# IMX291.net
KiCad netlist of a schematic drawn in Altium Designer
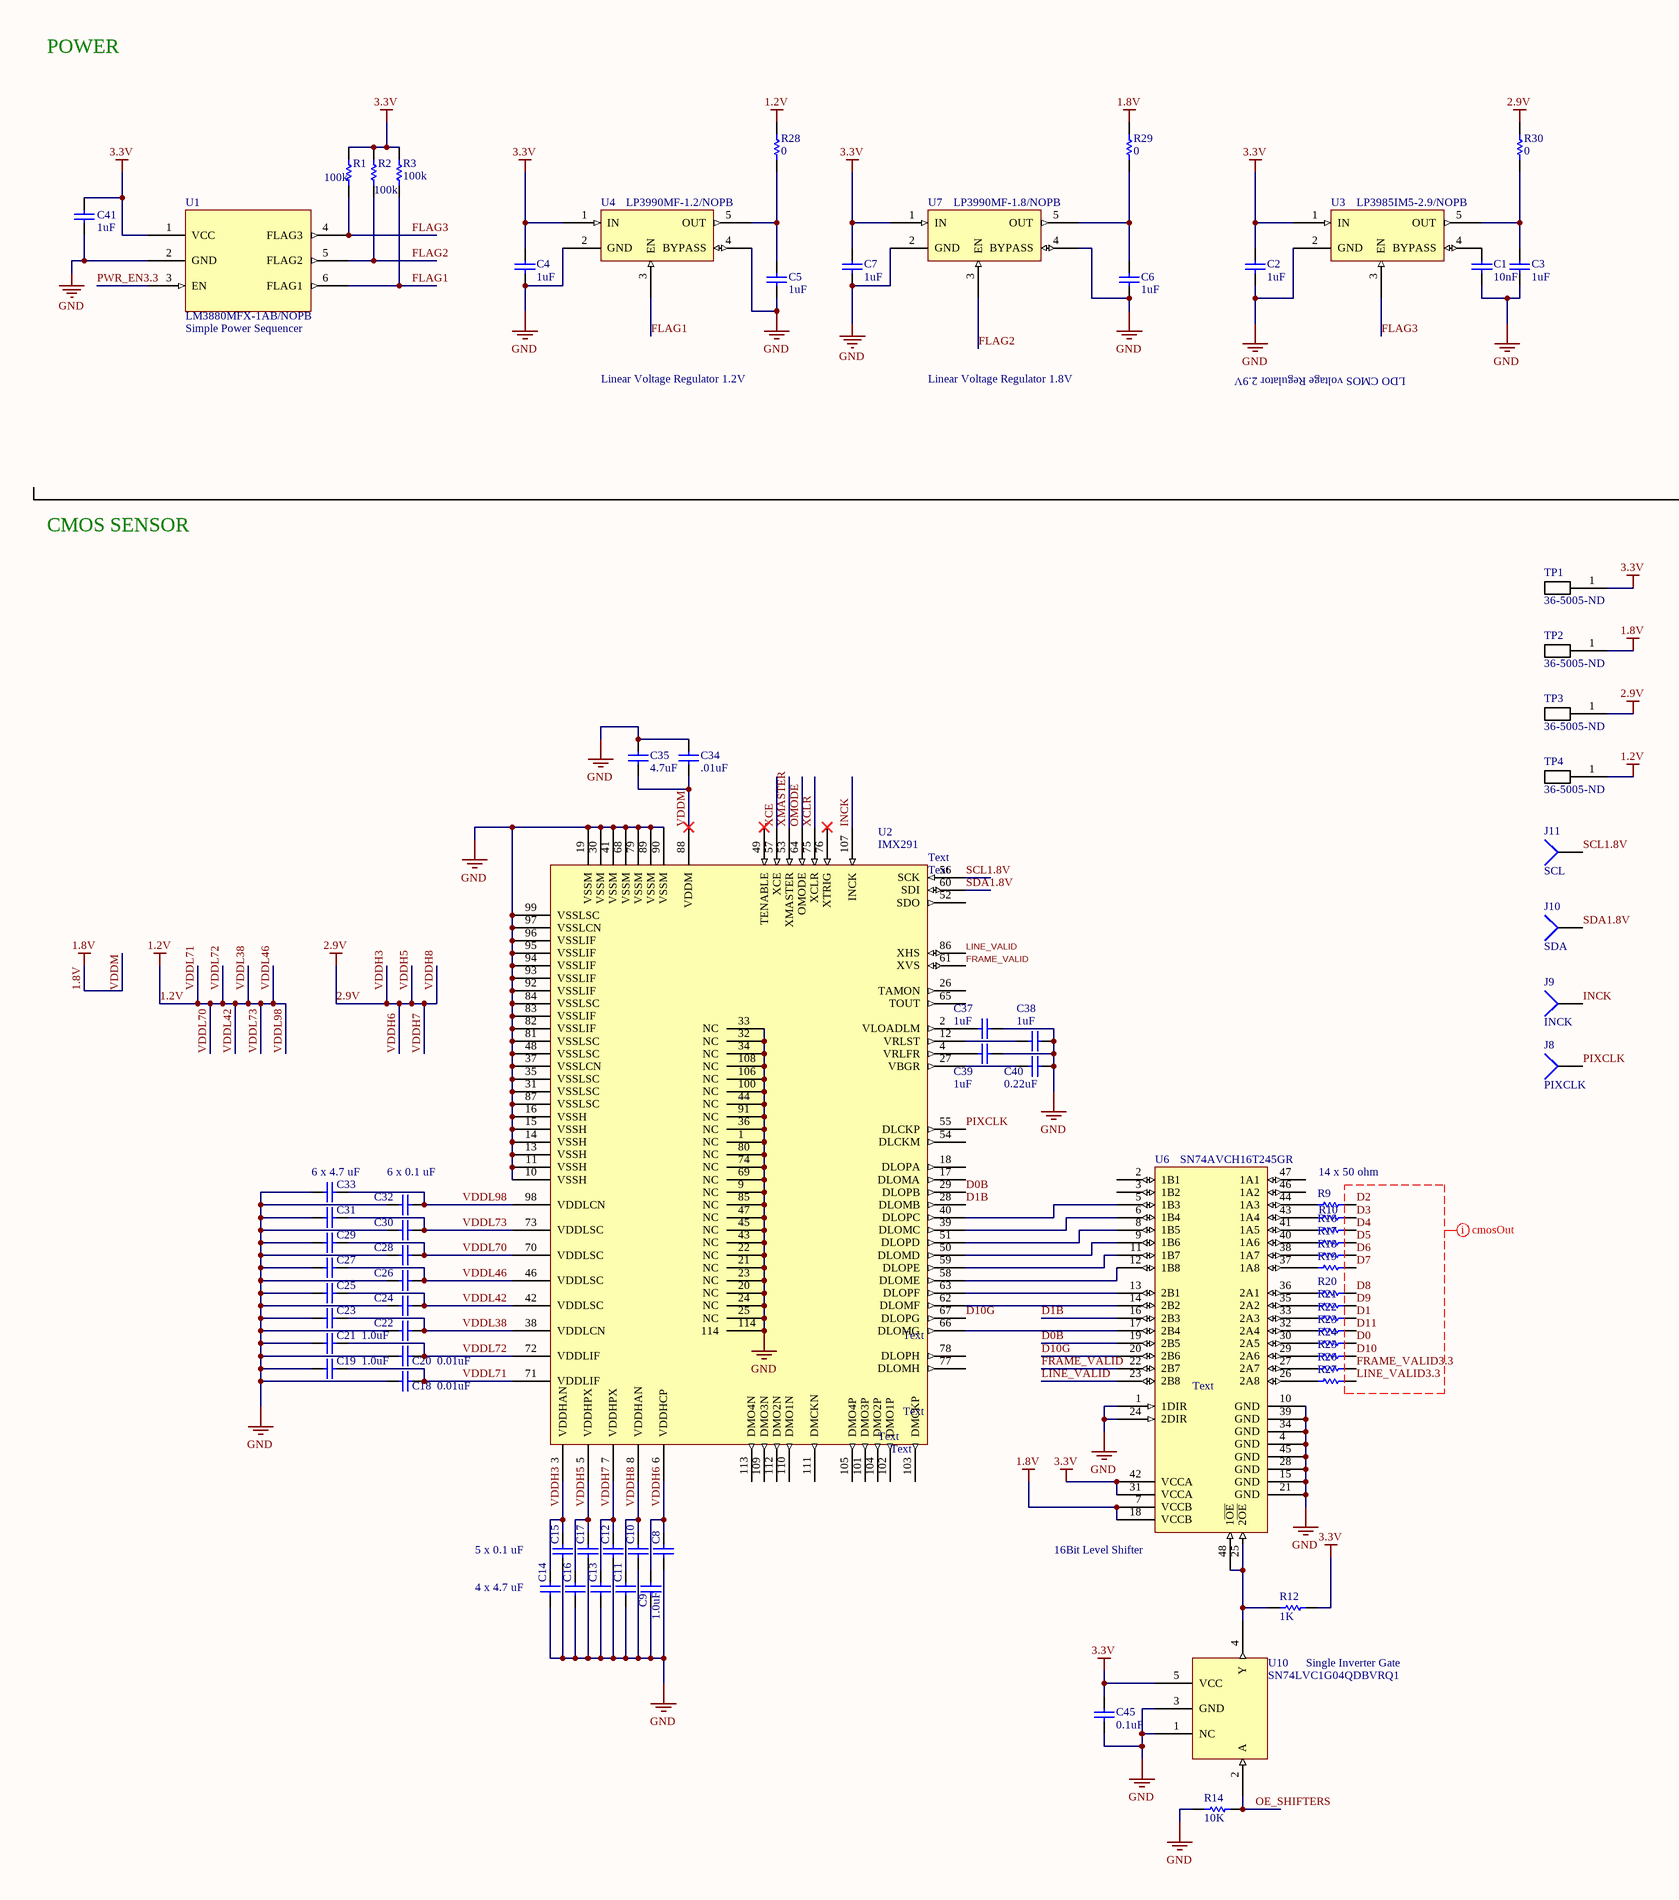
[diagram p0: IMX291.SchDoc, left]
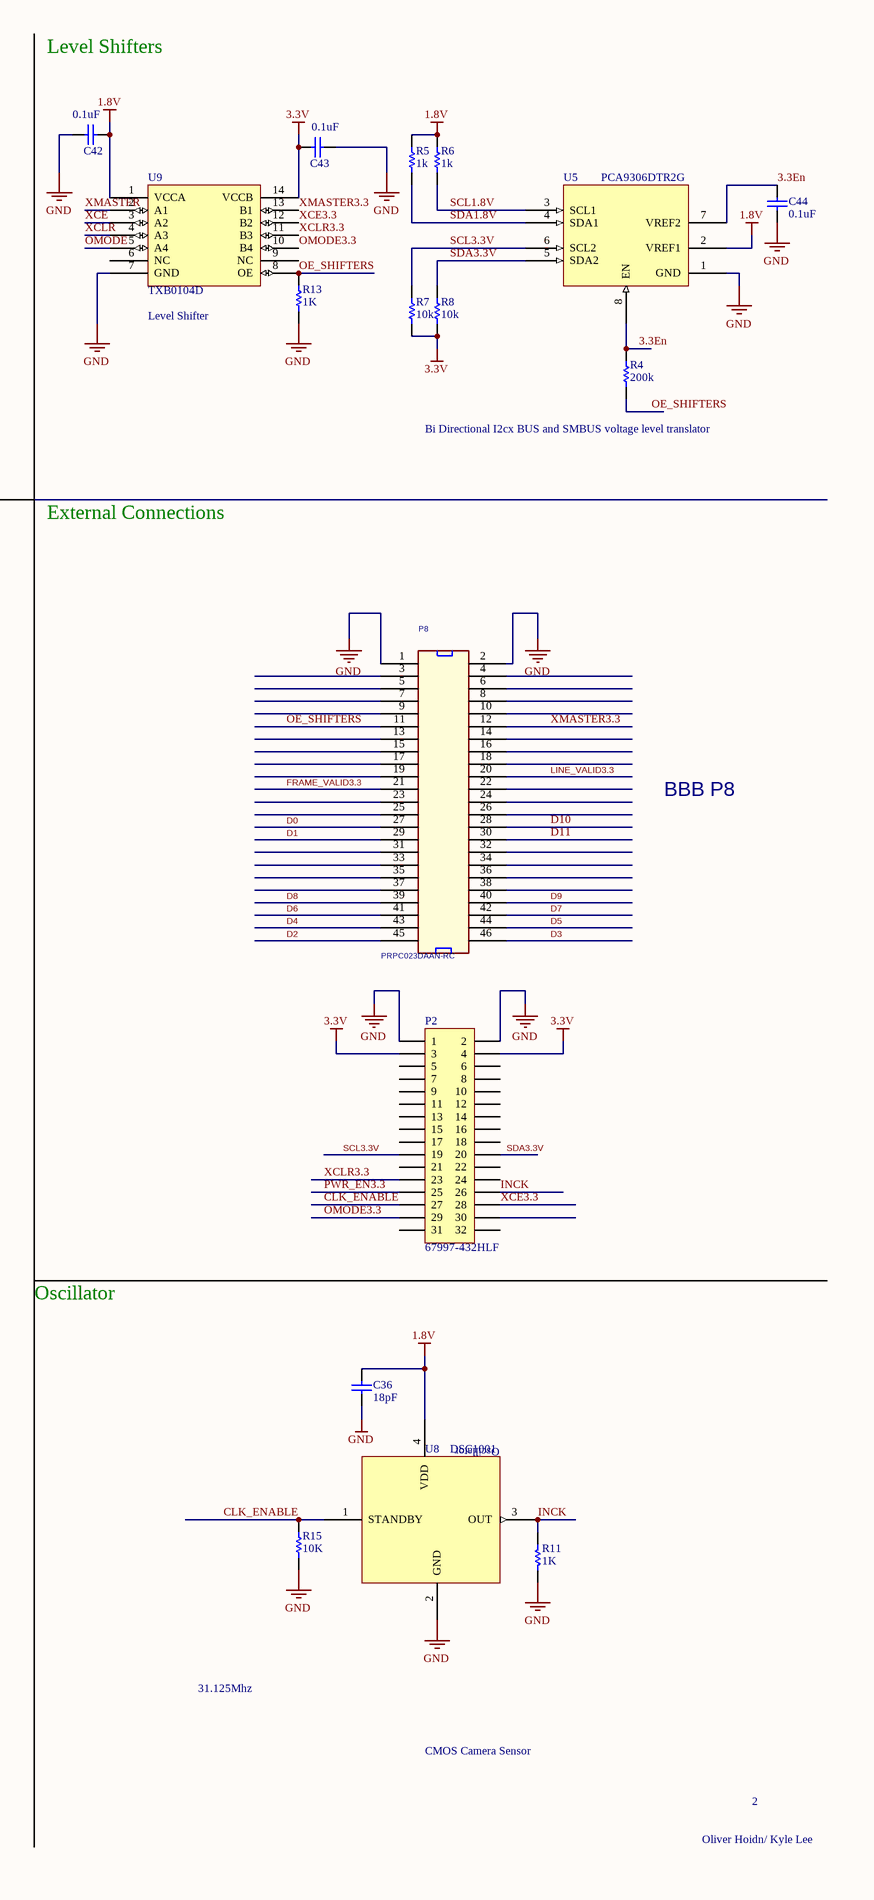
[diagram p1: IMX291.SchDoc, right]

(export (version "E")
  (design (tool "Eeschema 10.0.6"))
  (components
    (comp (ref "C1") (value "10nF") (footprint "0402") (libsource (lib "IMX291") (part "cap")))
    (comp (ref "C2") (value "1uF") (footprint "0402") (libsource (lib "IMX291") (part "cap")))
    (comp (ref "C3") (value "1uF") (footprint "0402") (libsource (lib "IMX291") (part "cap")))
    (comp (ref "C4") (value "1uF") (footprint "0402") (libsource (lib "IMX291") (part "cap")))
    (comp (ref "C5") (value "1uF") (footprint "0402") (libsource (lib "IMX291") (part "cap")))
    (comp (ref "C6") (value "1uF") (footprint "0402") (libsource (lib "IMX291") (part "cap")))
    (comp (ref "C7") (value "1uF") (footprint "0402") (libsource (lib "IMX291") (part "cap")))
    (comp (ref "C8") (value "0.1uF") (footprint "0402") (libsource (lib "IMX291") (part "cap")))
    (comp (ref "C9") (value "1.0uF") (footprint "0402") (libsource (lib "IMX291") (part "cap")))
    (comp (ref "C10") (value "0.1uF") (footprint "0402") (libsource (lib "IMX291") (part "cap")))
    (comp (ref "C11") (value "4.7uF") (footprint "0402") (libsource (lib "IMX291") (part "cap")))
    (comp (ref "C12") (value "0.1uF") (footprint "0402") (libsource (lib "IMX291") (part "cap")))
    (comp (ref "C13") (value "4.7uF") (footprint "0402") (libsource (lib "IMX291") (part "cap")))
    (comp (ref "C14") (value "4.7uF") (footprint "0402") (libsource (lib "IMX291") (part "cap")))
    (comp (ref "C15") (value "0.1uF") (footprint "0402") (libsource (lib "IMX291") (part "cap")))
    (comp (ref "C16") (value "4.7uF") (footprint "0402") (libsource (lib "IMX291") (part "cap")))
    (comp (ref "C17") (value "0.1uF") (footprint "0402") (libsource (lib "IMX291") (part "cap")))
    (comp (ref "C18") (value "0.01uF") (footprint "0402") (libsource (lib "IMX291") (part "cap")))
    (comp (ref "C19") (value "1.0uF") (footprint "0402") (libsource (lib "IMX291") (part "cap")))
    (comp (ref "C20") (value "0.01uF") (footprint "0402") (libsource (lib "IMX291") (part "cap")))
    (comp (ref "C21") (value "1.0uF") (footprint "0402") (libsource (lib "IMX291") (part "cap")))
    (comp (ref "C22") (value "0.1uF") (footprint "0402") (libsource (lib "IMX291") (part "cap")))
    (comp (ref "C23") (value "4.7uF") (footprint "0402") (libsource (lib "IMX291") (part "cap")))
    (comp (ref "C24") (value "0.1uF") (footprint "0402") (libsource (lib "IMX291") (part "cap")))
    (comp (ref "C25") (value "4.7uF") (footprint "0402") (libsource (lib "IMX291") (part "cap")))
    (comp (ref "C26") (value "0.1uF") (footprint "0402") (libsource (lib "IMX291") (part "cap")))
    (comp (ref "C27") (value "4.7uF") (footprint "0402") (libsource (lib "IMX291") (part "cap")))
    (comp (ref "C28") (value "0.1uF") (footprint "0402") (libsource (lib "IMX291") (part "cap")))
    (comp (ref "C29") (value "4.7uF") (footprint "0402") (libsource (lib "IMX291") (part "cap")))
    (comp (ref "C30") (value "0.1uF") (footprint "0402") (libsource (lib "IMX291") (part "cap")))
    (comp (ref "C31") (value "4.7uF") (footprint "0402") (libsource (lib "IMX291") (part "cap")))
    (comp (ref "C32") (value "0.1uF") (footprint "0402") (libsource (lib "IMX291") (part "cap")))
    (comp (ref "C33") (value "4.7uF") (footprint "0402") (libsource (lib "IMX291") (part "cap")))
    (comp (ref "C34") (value ".01uF") (footprint "0402") (libsource (lib "IMX291") (part "cap")))
    (comp (ref "C35") (value "4.7uF") (footprint "0402") (libsource (lib "IMX291") (part "cap")))
    (comp (ref "C36") (value "18pF") (footprint "0402") (libsource (lib "IMX291") (part "cap")))
    (comp (ref "C37") (value "1uF") (footprint "0402") (libsource (lib "IMX291") (part "cap")))
    (comp (ref "C38") (value "1uF") (footprint "0402") (libsource (lib "IMX291") (part "cap")))
    (comp (ref "C39") (value "1uF") (footprint "0402") (libsource (lib "IMX291") (part "cap")))
    (comp (ref "C40") (value "0.22uF") (footprint "0402") (libsource (lib "IMX291") (part "cap")))
    (comp (ref "C41") (value "1uF") (footprint "0402") (libsource (lib "IMX291") (part "cap")))
    (comp (ref "C42") (value "0.1uF") (footprint "0603") (libsource (lib "IMX291") (part "cap")))
    (comp (ref "C43") (value "0.1uF") (footprint "0603") (libsource (lib "IMX291") (part "cap")))
    (comp (ref "C44") (value "0.1uF") (footprint "0402") (libsource (lib "IMX291") (part "cap")))
    (comp (ref "C45") (value "0.1uF") (footprint "0402") (libsource (lib "IMX291") (part "cap")))
    (comp (ref "J8")
      (value "PIXCLK")
      (footprint "PIN1")
      (description "Socket")
      (fields (field (name "PUBLISHER") "Altium Limited"))
      (libsource (lib "IMX291") (part "Socket"))
    )
    (comp (ref "J9")
      (value "INCK")
      (footprint "PIN1")
      (description "Socket")
      (fields (field (name "PUBLISHER") "Altium Limited"))
      (libsource (lib "IMX291") (part "Socket"))
    )
    (comp (ref "J10")
      (value "SDA")
      (footprint "PIN1")
      (description "Socket")
      (fields (field (name "PUBLISHER") "Altium Limited"))
      (libsource (lib "IMX291") (part "Socket"))
    )
    (comp (ref "J11")
      (value "SCL")
      (footprint "PIN1")
      (description "Socket")
      (fields (field (name "PUBLISHER") "Altium Limited"))
      (libsource (lib "IMX291") (part "Socket"))
    )
    (comp (ref "P2")
      (value "67997-432HLF")
      (footprint "HDR2X16")
      (description "P9")
      (fields (field (name "PUBLISHER") "Altium Limited"))
      (libsource (lib "IMX291") (part "Header 16X2"))
    )
    (comp (ref "P8")
      (value "PRPC023DAAN-RC")
      (description "CONN HEADER FMAL 46PS.1\" DL GOLD")
      (fields
        (field (name "MANUFACTURER") "Sullins Connector Solutions")
        (field (name "MANUFACTURER PART NUMBER") "PPPC232LFBN-RC")
      )
      (libsource (lib "IMX291") (part "HDR_46_F_2_0.1_0.1"))
    )
    (comp (ref "R1")
      (value "100k")
      (footprint "0402")
      (description "resistor")
      (libsource (lib "") (part "res_1"))
    )
    (comp (ref "R2")
      (value "100k")
      (footprint "0402")
      (description "resistor")
      (libsource (lib "") (part "res_1"))
    )
    (comp (ref "R3")
      (value "100k")
      (footprint "0402")
      (description "resistor")
      (libsource (lib "") (part "res_1"))
    )
    (comp (ref "R4")
      (value "200k")
      (footprint "0402")
      (description "resistor")
      (libsource (lib "") (part "res_1"))
    )
    (comp (ref "R5")
      (value "1k")
      (footprint "0402")
      (description "resistor")
      (libsource (lib "") (part "res_1"))
    )
    (comp (ref "R6")
      (value "1k")
      (footprint "0402")
      (description "resistor")
      (libsource (lib "") (part "res_1"))
    )
    (comp (ref "R7")
      (value "10k")
      (footprint "0603")
      (description "resistor")
      (libsource (lib "") (part "res_1"))
    )
    (comp (ref "R8")
      (value "10k")
      (footprint "0603")
      (description "resistor")
      (libsource (lib "") (part "res_1"))
    )
    (comp (ref "R9") (value "50") (footprint "0402") (libsource (lib "IMX291") (part "res")))
    (comp (ref "R10") (value "50") (footprint "0402") (libsource (lib "IMX291") (part "res")))
    (comp (ref "R11") (value "1K") (footprint "0402") (libsource (lib "IMX291") (part "res")))
    (comp (ref "R12") (value "1K") (footprint "0402") (libsource (lib "IMX291") (part "res")))
    (comp (ref "R13") (value "1K") (footprint "0402") (libsource (lib "IMX291") (part "res")))
    (comp (ref "R14") (value "10K") (footprint "0402") (libsource (lib "IMX291") (part "res")))
    (comp (ref "R15") (value "10K") (footprint "0402") (libsource (lib "IMX291") (part "res")))
    (comp (ref "R16") (value "50") (footprint "0402") (libsource (lib "IMX291") (part "res")))
    (comp (ref "R17") (value "50") (footprint "0402") (libsource (lib "IMX291") (part "res")))
    (comp (ref "R18") (value "50") (footprint "0402") (libsource (lib "IMX291") (part "res")))
    (comp (ref "R19") (value "50") (footprint "0402") (libsource (lib "IMX291") (part "res")))
    (comp (ref "R20") (value "50") (footprint "0402") (libsource (lib "IMX291") (part "res")))
    (comp (ref "R21") (value "50") (footprint "0402") (libsource (lib "IMX291") (part "res")))
    (comp (ref "R22") (value "50") (footprint "0402") (libsource (lib "IMX291") (part "res")))
    (comp (ref "R23") (value "50") (footprint "0402") (libsource (lib "IMX291") (part "res")))
    (comp (ref "R24") (value "50") (footprint "0402") (libsource (lib "IMX291") (part "res")))
    (comp (ref "R25") (value "50") (footprint "0402") (libsource (lib "IMX291") (part "res")))
    (comp (ref "R26") (value "50") (footprint "0402") (libsource (lib "IMX291") (part "res")))
    (comp (ref "R27") (value "50") (footprint "0402") (libsource (lib "IMX291") (part "res")))
    (comp (ref "R28") (value "0") (footprint "0603") (libsource (lib "IMX291") (part "res")))
    (comp (ref "R29") (value "0") (footprint "0603") (libsource (lib "IMX291") (part "res")))
    (comp (ref "R30") (value "0") (footprint "0603") (libsource (lib "IMX291") (part "res")))
    (comp (ref "TP1")
      (value "36-5005-ND")
      (footprint "testPoint")
      (description "testPoint")
      (libsource (lib "IMX291") (part "testPoint"))
    )
    (comp (ref "TP2")
      (value "36-5005-ND")
      (footprint "testPoint")
      (description "testPoint")
      (libsource (lib "IMX291") (part "testPoint"))
    )
    (comp (ref "TP3")
      (value "36-5005-ND")
      (footprint "testPoint")
      (description "testPoint")
      (libsource (lib "IMX291") (part "testPoint"))
    )
    (comp (ref "TP4")
      (value "36-5005-ND")
      (footprint "testPoint")
      (description "testPoint")
      (libsource (lib "IMX291") (part "testPoint"))
    )
    (comp (ref "U1")
      (value "LM3880MFX-1AB/NOPB")
      (footprint "SOT23-6_M")
      (libsource (lib "IMX291") (part "LM3880"))
    )
    (comp (ref "U2") (value "IMX291") (footprint "SOCKET") (libsource (lib "IMX291") (part "IMX291")))
    (comp (ref "U3")
      (value "LP3985IM5-2.9/NOPB")
      (footprint "DBV005")
      (libsource (lib "IMX291") (part "LP3985"))
    )
    (comp (ref "U4")
      (value "LP3990MF-1.2/NOPB")
      (footprint "DBV005")
      (libsource (lib "IMX291") (part "LP3990"))
    )
    (comp (ref "U5") (value "PCA9306DTR2G") (footprint "TSOPP8") (libsource (lib "IMX291") (part "PCA9306")))
    (comp (ref "U6")
      (value "SN74AVCH16T245GR")
      (footprint "TSSOP48")
      (libsource (lib "IMX291") (part "SN74AVCH16T245"))
    )
    (comp (ref "U7")
      (value "LP3990MF-1.8/NOPB")
      (footprint "DBV005")
      (libsource (lib "IMX291") (part "LP3990"))
    )
    (comp (ref "U8")
      (value "DSC1001")
      (footprint "DSC1001 2.5x.2.0mm")
      (libsource (lib "IMX291") (part "DSC1001"))
    )
    (comp (ref "U9") (value "TXB0104D") (footprint "SOIC_14") (libsource (lib "IMX291") (part "TXB0104")))
    (comp (ref "U10")
      (value "SN74LVC1G04QDBVRQ1")
      (footprint "DBV005")
      (libsource (lib "IMX291") (part "SN74LVC1G04"))
    )
  )
  (nets
    (net (code "1") (name "/3.3En") (class "Default")
      (node (ref "C44") (pin "1") (pinfunction "1_1") (pintype "passive"))
      (node (ref "R4") (pin "2") (pinfunction "2_2") (pintype "passive"))
      (node (ref "U5") (pin "7") (pinfunction "VREF2_7") (pintype "power_in"))
      (node (ref "U5") (pin "8") (pinfunction "EN_8") (pintype "input"))
    )
    (net (code "2") (name "/CLK_ENABLE") (class "Default")
      (node (ref "P2") (pin "27") (pinfunction "27_27") (pintype "passive"))
      (node (ref "R15") (pin "2") (pinfunction "2_2") (pintype "passive"))
      (node (ref "U8") (pin "1") (pinfunction "STANDBY_1") (pintype "passive"))
    )
    (net (code "3") (name "/D0") (class "Default")
      (node (ref "P8") (pin "27") (pinfunction "14_27") (pintype "passive"))
      (node (ref "R24") (pin "2") (pinfunction "2_2") (pintype "passive"))
    )
    (net (code "4") (name "/D0B") (class "Default")
      (node (ref "U2") (pin "29") (pinfunction "DLOPB_29") (pintype "output"))
      (node (ref "U6") (pin "19") (pinfunction "2B5_19") (pintype "bidirectional"))
    )
    (net (code "5") (name "/D1") (class "Default")
      (node (ref "P8") (pin "29") (pinfunction "15_29") (pintype "passive"))
      (node (ref "R22") (pin "2") (pinfunction "2_2") (pintype "passive"))
    )
    (net (code "6") (name "/D1B") (class "Default")
      (node (ref "U2") (pin "28") (pinfunction "DLOMB_28") (pintype "output"))
      (node (ref "U6") (pin "16") (pinfunction "2B3_16") (pintype "bidirectional"))
    )
    (net (code "7") (name "/D2") (class "Default")
      (node (ref "P8") (pin "45") (pinfunction "23_45") (pintype "passive"))
      (node (ref "R9") (pin "2") (pinfunction "2_2") (pintype "passive"))
    )
    (net (code "8") (name "/D3") (class "Default")
      (node (ref "P8") (pin "46") (pinfunction "48_46") (pintype "passive"))
      (node (ref "R10") (pin "2") (pinfunction "2_2") (pintype "passive"))
    )
    (net (code "9") (name "/D4") (class "Default")
      (node (ref "P8") (pin "43") (pinfunction "22_43") (pintype "passive"))
      (node (ref "R16") (pin "2") (pinfunction "2_2") (pintype "passive"))
    )
    (net (code "10") (name "/D5") (class "Default")
      (node (ref "P8") (pin "44") (pinfunction "47_44") (pintype "passive"))
      (node (ref "R17") (pin "2") (pinfunction "2_2") (pintype "passive"))
    )
    (net (code "11") (name "/D6") (class "Default")
      (node (ref "P8") (pin "41") (pinfunction "21_41") (pintype "passive"))
      (node (ref "R18") (pin "2") (pinfunction "2_2") (pintype "passive"))
    )
    (net (code "12") (name "/D7") (class "Default")
      (node (ref "P8") (pin "42") (pinfunction "46_42") (pintype "passive"))
      (node (ref "R19") (pin "2") (pinfunction "2_2") (pintype "passive"))
    )
    (net (code "13") (name "/D8") (class "Default")
      (node (ref "P8") (pin "39") (pinfunction "20_39") (pintype "passive"))
      (node (ref "R20") (pin "2") (pinfunction "2_2") (pintype "passive"))
    )
    (net (code "14") (name "/D9") (class "Default")
      (node (ref "P8") (pin "40") (pinfunction "45_40") (pintype "passive"))
      (node (ref "R21") (pin "2") (pinfunction "2_2") (pintype "passive"))
    )
    (net (code "15") (name "/D10") (class "Default")
      (node (ref "P8") (pin "28") (pinfunction "39_28") (pintype "passive"))
      (node (ref "R25") (pin "2") (pinfunction "2_2") (pintype "passive"))
    )
    (net (code "16") (name "/D10G") (class "Default")
      (node (ref "U2") (pin "67") (pinfunction "DLOPG_67") (pintype "output"))
      (node (ref "U6") (pin "20") (pinfunction "2B6_20") (pintype "bidirectional"))
    )
    (net (code "17") (name "/D11") (class "Default")
      (node (ref "P8") (pin "30") (pinfunction "40_30") (pintype "passive"))
      (node (ref "R23") (pin "2") (pinfunction "2_2") (pintype "passive"))
    )
    (net (code "18") (name "/FLAG1") (class "Default")
      (node (ref "R3") (pin "1") (pinfunction "1_1") (pintype "passive"))
      (node (ref "U1") (pin "6") (pinfunction "FLAG1_6") (pintype "output"))
      (node (ref "U4") (pin "3") (pinfunction "EN_3") (pintype "input"))
    )
    (net (code "19") (name "/FLAG2") (class "Default")
      (node (ref "R2") (pin "1") (pinfunction "1_1") (pintype "passive"))
      (node (ref "U1") (pin "5") (pinfunction "FLAG2_5") (pintype "output"))
      (node (ref "U7") (pin "3") (pinfunction "EN_3") (pintype "input"))
    )
    (net (code "20") (name "/FLAG3") (class "Default")
      (node (ref "R1") (pin "1") (pinfunction "1_1") (pintype "passive"))
      (node (ref "U1") (pin "4") (pinfunction "FLAG3_4") (pintype "output"))
      (node (ref "U3") (pin "3") (pinfunction "EN_3") (pintype "input"))
    )
    (net (code "21") (name "/FRAME_VALID") (class "Default")
      (node (ref "U2") (pin "61") (pinfunction "XVS_61") (pintype "bidirectional"))
      (node (ref "U6") (pin "22") (pinfunction "2B7_22") (pintype "bidirectional"))
    )
    (net (code "22") (name "/FRAME_VALID3.3") (class "Default")
      (node (ref "P8") (pin "21") (pinfunction "11_21") (pintype "passive"))
      (node (ref "R26") (pin "2") (pinfunction "2_2") (pintype "passive"))
    )
    (net (code "23") (name "/INCK") (class "Default")
      (node (ref "J9") (pin "1") (pinfunction "1_1") (pintype "passive"))
      (node (ref "P2") (pin "26") (pinfunction "26_26") (pintype "passive"))
      (node (ref "R11") (pin "2") (pinfunction "2_2") (pintype "passive"))
      (node (ref "U2") (pin "107") (pinfunction "INCK_107") (pintype "input"))
      (node (ref "U8") (pin "3") (pinfunction "OUT_3") (pintype "output"))
    )
    (net (code "24") (name "/LINE_VALID") (class "Default")
      (node (ref "U2") (pin "86") (pinfunction "XHS_86") (pintype "bidirectional"))
      (node (ref "U6") (pin "23") (pinfunction "2B8_23") (pintype "bidirectional"))
    )
    (net (code "25") (name "/LINE_VALID3.3") (class "Default")
      (node (ref "P8") (pin "20") (pinfunction "35_20") (pintype "passive"))
      (node (ref "R27") (pin "2") (pinfunction "2_2") (pintype "passive"))
    )
    (net (code "26") (name "/OE_SHIFTERS") (class "Default")
      (node (ref "P8") (pin "11") (pinfunction "6_11") (pintype "passive"))
      (node (ref "R13") (pin "2") (pinfunction "2_2") (pintype "passive"))
      (node (ref "R14") (pin "2") (pinfunction "2_2") (pintype "passive"))
      (node (ref "R4") (pin "1") (pinfunction "1_1") (pintype "passive"))
      (node (ref "U10") (pin "2") (pinfunction "A_2") (pintype "input"))
      (node (ref "U9") (pin "8") (pinfunction "OE_8") (pintype "bidirectional"))
    )
    (net (code "27") (name "/OMODE") (class "Default")
      (node (ref "U2") (pin "64") (pinfunction "OMODE_64") (pintype "input"))
      (node (ref "U9") (pin "5") (pinfunction "A4_5") (pintype "bidirectional"))
    )
    (net (code "28") (name "/OMODE3.3") (class "Default")
      (node (ref "P2") (pin "29") (pinfunction "29_29") (pintype "passive"))
      (node (ref "U9") (pin "10") (pinfunction "B4_10") (pintype "bidirectional"))
    )
    (net (code "29") (name "/PIXCLK") (class "Default")
      (node (ref "J8") (pin "1") (pinfunction "1_1") (pintype "passive"))
      (node (ref "U2") (pin "55") (pinfunction "DLCKP_55") (pintype "output"))
    )
    (net (code "30") (name "/PWR_EN3.3") (class "Default")
      (node (ref "P2") (pin "25") (pinfunction "25_25") (pintype "passive"))
      (node (ref "U1") (pin "3") (pinfunction "EN_3") (pintype "input"))
    )
    (net (code "31") (name "/SCL1.8V") (class "Default")
      (node (ref "J11") (pin "1") (pinfunction "1_1") (pintype "passive"))
      (node (ref "R6") (pin "1") (pinfunction "1_1") (pintype "passive"))
      (node (ref "U2") (pin "56") (pinfunction "SCK_56") (pintype "input"))
      (node (ref "U5") (pin "3") (pinfunction "SCL1_3") (pintype "input"))
    )
    (net (code "32") (name "/SCL3.3V") (class "Default")
      (node (ref "P2") (pin "19") (pinfunction "19_19") (pintype "passive"))
      (node (ref "R7") (pin "2") (pinfunction "2_2") (pintype "passive"))
      (node (ref "U5") (pin "6") (pinfunction "SCL2_6") (pintype "input"))
    )
    (net (code "33") (name "/SDA1.8V") (class "Default")
      (node (ref "J10") (pin "1") (pinfunction "1_1") (pintype "passive"))
      (node (ref "R5") (pin "1") (pinfunction "1_1") (pintype "passive"))
      (node (ref "U2") (pin "60") (pinfunction "SDI_60") (pintype "bidirectional"))
      (node (ref "U5") (pin "4") (pinfunction "SDA1_4") (pintype "input"))
    )
    (net (code "34") (name "/SDA3.3V") (class "Default")
      (node (ref "P2") (pin "20") (pinfunction "20_20") (pintype "passive"))
      (node (ref "R8") (pin "2") (pinfunction "2_2") (pintype "passive"))
      (node (ref "U5") (pin "5") (pinfunction "SDA2_5") (pintype "input"))
    )
    (net (code "35") (name "/XCE") (class "Default")
      (node (ref "U2") (pin "57") (pinfunction "XCE_57") (pintype "input"))
      (node (ref "U9") (pin "3") (pinfunction "A2_3") (pintype "bidirectional"))
    )
    (net (code "36") (name "/XCE3.3") (class "Default")
      (node (ref "P2") (pin "28") (pinfunction "28_28") (pintype "passive"))
      (node (ref "U9") (pin "12") (pinfunction "B2_12") (pintype "bidirectional"))
    )
    (net (code "37") (name "/XCLR") (class "Default")
      (node (ref "U2") (pin "75") (pinfunction "XCLR_75") (pintype "input"))
      (node (ref "U9") (pin "4") (pinfunction "A3_4") (pintype "bidirectional"))
    )
    (net (code "38") (name "/XCLR3.3") (class "Default")
      (node (ref "P2") (pin "23") (pinfunction "23_23") (pintype "passive"))
      (node (ref "U9") (pin "11") (pinfunction "B3_11") (pintype "bidirectional"))
    )
    (net (code "39") (name "/XMASTER") (class "Default")
      (node (ref "U2") (pin "53") (pinfunction "XMASTER_53") (pintype "input"))
      (node (ref "U9") (pin "2") (pinfunction "A1_2") (pintype "bidirectional"))
    )
    (net (code "40") (name "/XMASTER3.3") (class "Default")
      (node (ref "P8") (pin "12") (pinfunction "31_12") (pintype "passive"))
      (node (ref "U9") (pin "13") (pinfunction "B1_13") (pintype "bidirectional"))
    )
    (net (code "41") (name "1.2V") (class "Default")
      (node (ref "C18") (pin "2") (pinfunction "2_2") (pintype "passive"))
      (node (ref "C19") (pin "2") (pinfunction "2_2") (pintype "passive"))
      (node (ref "C20") (pin "2") (pinfunction "2_2") (pintype "passive"))
      (node (ref "C21") (pin "2") (pinfunction "2_2") (pintype "passive"))
      (node (ref "C22") (pin "2") (pinfunction "2_2") (pintype "passive"))
      (node (ref "C23") (pin "2") (pinfunction "2_2") (pintype "passive"))
      (node (ref "C24") (pin "2") (pinfunction "2_2") (pintype "passive"))
      (node (ref "C25") (pin "2") (pinfunction "2_2") (pintype "passive"))
      (node (ref "C26") (pin "2") (pinfunction "2_2") (pintype "passive"))
      (node (ref "C27") (pin "2") (pinfunction "2_2") (pintype "passive"))
      (node (ref "C28") (pin "2") (pinfunction "2_2") (pintype "passive"))
      (node (ref "C29") (pin "2") (pinfunction "2_2") (pintype "passive"))
      (node (ref "C30") (pin "2") (pinfunction "2_2") (pintype "passive"))
      (node (ref "C31") (pin "2") (pinfunction "2_2") (pintype "passive"))
      (node (ref "C32") (pin "2") (pinfunction "2_2") (pintype "passive"))
      (node (ref "C33") (pin "2") (pinfunction "2_2") (pintype "passive"))
      (node (ref "R28") (pin "2") (pinfunction "2_2") (pintype "passive"))
      (node (ref "U2") (pin "38") (pinfunction "VDDLCN_38") (pintype "power_in"))
      (node (ref "U2") (pin "42") (pinfunction "VDDLSC_42") (pintype "power_in"))
      (node (ref "U2") (pin "46") (pinfunction "VDDLSC_46") (pintype "power_in"))
      (node (ref "U2") (pin "70") (pinfunction "VDDLSC_70") (pintype "power_in"))
      (node (ref "U2") (pin "71") (pinfunction "VDDLIF_71") (pintype "power_in"))
      (node (ref "U2") (pin "72") (pinfunction "VDDLIF_72") (pintype "power_in"))
      (node (ref "U2") (pin "73") (pinfunction "VDDLSC_73") (pintype "power_in"))
      (node (ref "U2") (pin "98") (pinfunction "VDDLCN_98") (pintype "power_in"))
    )
    (net (code "42") (name "1.8V") (class "Default")
      (node (ref "C34") (pin "1") (pinfunction "1_1") (pintype "passive"))
      (node (ref "C35") (pin "1") (pinfunction "1_1") (pintype "passive"))
      (node (ref "C36") (pin "2") (pinfunction "2_2") (pintype "passive"))
      (node (ref "C42") (pin "2") (pinfunction "2_2") (pintype "passive"))
      (node (ref "R29") (pin "2") (pinfunction "2_2") (pintype "passive"))
      (node (ref "R5") (pin "2") (pinfunction "2_2") (pintype "passive"))
      (node (ref "R6") (pin "2") (pinfunction "2_2") (pintype "passive"))
      (node (ref "U2") (pin "88") (pinfunction "VDDM_88") (pintype "power_in"))
      (node (ref "U5") (pin "2") (pinfunction "VREF1_2") (pintype "power_in"))
      (node (ref "U6") (pin "18") (pinfunction "VCCB_18") (pintype "power_in"))
      (node (ref "U6") (pin "7") (pinfunction "VCCB_7") (pintype "power_in"))
      (node (ref "U8") (pin "4") (pinfunction "VDD_4") (pintype "passive"))
      (node (ref "U9") (pin "1") (pinfunction "VCCA_1") (pintype "power_in"))
    )
    (net (code "43") (name "2.9V") (class "Default")
      (node (ref "C10") (pin "2") (pinfunction "2_2") (pintype "passive"))
      (node (ref "C11") (pin "2") (pinfunction "2_2") (pintype "passive"))
      (node (ref "C12") (pin "2") (pinfunction "2_2") (pintype "passive"))
      (node (ref "C13") (pin "2") (pinfunction "2_2") (pintype "passive"))
      (node (ref "C14") (pin "2") (pinfunction "2_2") (pintype "passive"))
      (node (ref "C15") (pin "2") (pinfunction "2_2") (pintype "passive"))
      (node (ref "C16") (pin "2") (pinfunction "2_2") (pintype "passive"))
      (node (ref "C17") (pin "2") (pinfunction "2_2") (pintype "passive"))
      (node (ref "C8") (pin "1") (pinfunction "1_1") (pintype "passive"))
      (node (ref "C9") (pin "1") (pinfunction "1_1") (pintype "passive"))
      (node (ref "R30") (pin "2") (pinfunction "2_2") (pintype "passive"))
      (node (ref "U2") (pin "3") (pinfunction "VDDHAN_3") (pintype "power_in"))
      (node (ref "U2") (pin "5") (pinfunction "VDDHPX_5") (pintype "power_in"))
      (node (ref "U2") (pin "6") (pinfunction "VDDHCP_6") (pintype "power_in"))
      (node (ref "U2") (pin "7") (pinfunction "VDDHPX_7") (pintype "power_in"))
      (node (ref "U2") (pin "8") (pinfunction "VDDHAN_8") (pintype "power_in"))
    )
    (net (code "44") (name "3.3V") (class "Default")
      (node (ref "C2") (pin "1") (pinfunction "1_1") (pintype "passive"))
      (node (ref "C4") (pin "1") (pinfunction "1_1") (pintype "passive"))
      (node (ref "C41") (pin "2") (pinfunction "2_2") (pintype "passive"))
      (node (ref "C43") (pin "1") (pinfunction "1_1") (pintype "passive"))
      (node (ref "C45") (pin "1") (pinfunction "1_1") (pintype "passive"))
      (node (ref "C7") (pin "1") (pinfunction "1_1") (pintype "passive"))
      (node (ref "P2") (pin "3") (pinfunction "3_3") (pintype "passive"))
      (node (ref "P2") (pin "4") (pinfunction "4_4") (pintype "passive"))
      (node (ref "R1") (pin "2") (pinfunction "2_2") (pintype "passive"))
      (node (ref "R12") (pin "2") (pinfunction "2_2") (pintype "passive"))
      (node (ref "R2") (pin "2") (pinfunction "2_2") (pintype "passive"))
      (node (ref "R3") (pin "2") (pinfunction "2_2") (pintype "passive"))
      (node (ref "R7") (pin "1") (pinfunction "1_1") (pintype "passive"))
      (node (ref "R8") (pin "1") (pinfunction "1_1") (pintype "passive"))
      (node (ref "U1") (pin "1") (pinfunction "VCC_1") (pintype "power_in"))
      (node (ref "U10") (pin "5") (pinfunction "VCC_5") (pintype "power_in"))
      (node (ref "U3") (pin "1") (pinfunction "IN_1") (pintype "input"))
      (node (ref "U4") (pin "1") (pinfunction "IN_1") (pintype "input"))
      (node (ref "U6") (pin "31") (pinfunction "VCCA_31") (pintype "power_in"))
      (node (ref "U6") (pin "42") (pinfunction "VCCA_42") (pintype "power_in"))
      (node (ref "U7") (pin "1") (pinfunction "IN_1") (pintype "input"))
      (node (ref "U9") (pin "14") (pinfunction "VCCB_14") (pintype "power_in"))
    )
    (net (code "45") (name "GND") (class "Default")
      (node (ref "C1") (pin "2") (pinfunction "2_2") (pintype "passive"))
      (node (ref "C10") (pin "1") (pinfunction "1_1") (pintype "passive"))
      (node (ref "C11") (pin "1") (pinfunction "1_1") (pintype "passive"))
      (node (ref "C12") (pin "1") (pinfunction "1_1") (pintype "passive"))
      (node (ref "C13") (pin "1") (pinfunction "1_1") (pintype "passive"))
      (node (ref "C14") (pin "1") (pinfunction "1_1") (pintype "passive"))
      (node (ref "C15") (pin "1") (pinfunction "1_1") (pintype "passive"))
      (node (ref "C16") (pin "1") (pinfunction "1_1") (pintype "passive"))
      (node (ref "C17") (pin "1") (pinfunction "1_1") (pintype "passive"))
      (node (ref "C18") (pin "1") (pinfunction "1_1") (pintype "passive"))
      (node (ref "C19") (pin "1") (pinfunction "1_1") (pintype "passive"))
      (node (ref "C2") (pin "2") (pinfunction "2_2") (pintype "passive"))
      (node (ref "C20") (pin "1") (pinfunction "1_1") (pintype "passive"))
      (node (ref "C21") (pin "1") (pinfunction "1_1") (pintype "passive"))
      (node (ref "C22") (pin "1") (pinfunction "1_1") (pintype "passive"))
      (node (ref "C23") (pin "1") (pinfunction "1_1") (pintype "passive"))
      (node (ref "C24") (pin "1") (pinfunction "1_1") (pintype "passive"))
      (node (ref "C25") (pin "1") (pinfunction "1_1") (pintype "passive"))
      (node (ref "C26") (pin "1") (pinfunction "1_1") (pintype "passive"))
      (node (ref "C27") (pin "1") (pinfunction "1_1") (pintype "passive"))
      (node (ref "C28") (pin "1") (pinfunction "1_1") (pintype "passive"))
      (node (ref "C29") (pin "1") (pinfunction "1_1") (pintype "passive"))
      (node (ref "C3") (pin "1") (pinfunction "1_1") (pintype "passive"))
      (node (ref "C30") (pin "1") (pinfunction "1_1") (pintype "passive"))
      (node (ref "C31") (pin "1") (pinfunction "1_1") (pintype "passive"))
      (node (ref "C32") (pin "1") (pinfunction "1_1") (pintype "passive"))
      (node (ref "C33") (pin "1") (pinfunction "1_1") (pintype "passive"))
      (node (ref "C34") (pin "2") (pinfunction "2_2") (pintype "passive"))
      (node (ref "C35") (pin "2") (pinfunction "2_2") (pintype "passive"))
      (node (ref "C36") (pin "1") (pinfunction "1_1") (pintype "passive"))
      (node (ref "C37") (pin "2") (pinfunction "2_2") (pintype "passive"))
      (node (ref "C38") (pin "2") (pinfunction "2_2") (pintype "passive"))
      (node (ref "C39") (pin "2") (pinfunction "2_2") (pintype "passive"))
      (node (ref "C4") (pin "2") (pinfunction "2_2") (pintype "passive"))
      (node (ref "C40") (pin "2") (pinfunction "2_2") (pintype "passive"))
      (node (ref "C41") (pin "1") (pinfunction "1_1") (pintype "passive"))
      (node (ref "C42") (pin "1") (pinfunction "1_1") (pintype "passive"))
      (node (ref "C43") (pin "2") (pinfunction "2_2") (pintype "passive"))
      (node (ref "C44") (pin "2") (pinfunction "2_2") (pintype "passive"))
      (node (ref "C45") (pin "2") (pinfunction "2_2") (pintype "passive"))
      (node (ref "C5") (pin "1") (pinfunction "1_1") (pintype "passive"))
      (node (ref "C6") (pin "1") (pinfunction "1_1") (pintype "passive"))
      (node (ref "C7") (pin "2") (pinfunction "2_2") (pintype "passive"))
      (node (ref "C8") (pin "2") (pinfunction "2_2") (pintype "passive"))
      (node (ref "C9") (pin "2") (pinfunction "2_2") (pintype "passive"))
      (node (ref "P2") (pin "1") (pinfunction "1_1") (pintype "passive"))
      (node (ref "P2") (pin "2") (pinfunction "2_2") (pintype "passive"))
      (node (ref "P8") (pin "1") (pinfunction "1_1") (pintype "passive"))
      (node (ref "P8") (pin "2") (pinfunction "26_2") (pintype "passive"))
      (node (ref "R11") (pin "1") (pinfunction "1_1") (pintype "passive"))
      (node (ref "R13") (pin "1") (pinfunction "1_1") (pintype "passive"))
      (node (ref "R14") (pin "1") (pinfunction "1_1") (pintype "passive"))
      (node (ref "R15") (pin "1") (pinfunction "1_1") (pintype "passive"))
      (node (ref "U1") (pin "2") (pinfunction "GND_2") (pintype "power_in"))
      (node (ref "U10") (pin "1") (pinfunction "NC_1") (pintype "passive"))
      (node (ref "U10") (pin "3") (pinfunction "GND_3") (pintype "power_in"))
      (node (ref "U2") (pin "1") (pinfunction "NC_1") (pintype "passive"))
      (node (ref "U2") (pin "10") (pinfunction "VSSH_10") (pintype "power_in"))
      (node (ref "U2") (pin "100") (pinfunction "NC_100") (pintype "passive"))
      (node (ref "U2") (pin "106") (pinfunction "NC_106") (pintype "passive"))
      (node (ref "U2") (pin "108") (pinfunction "NC_108") (pintype "passive"))
      (node (ref "U2") (pin "11") (pinfunction "VSSH_11") (pintype "power_in"))
      (node (ref "U2") (pin "114") (pinfunction "114_114") (pintype "passive"))
      (node (ref "U2") (pin "13") (pinfunction "VSSH_13") (pintype "power_in"))
      (node (ref "U2") (pin "14") (pinfunction "VSSH_14") (pintype "power_in"))
      (node (ref "U2") (pin "15") (pinfunction "VSSH_15") (pintype "power_in"))
      (node (ref "U2") (pin "16") (pinfunction "VSSH_16") (pintype "power_in"))
      (node (ref "U2") (pin "19") (pinfunction "VSSM_19") (pintype "power_in"))
      (node (ref "U2") (pin "20") (pinfunction "NC_20") (pintype "passive"))
      (node (ref "U2") (pin "21") (pinfunction "NC_21") (pintype "passive"))
      (node (ref "U2") (pin "22") (pinfunction "NC_22") (pintype "passive"))
      (node (ref "U2") (pin "23") (pinfunction "NC_23") (pintype "passive"))
      (node (ref "U2") (pin "24") (pinfunction "NC_24") (pintype "passive"))
      (node (ref "U2") (pin "25") (pinfunction "NC_25") (pintype "passive"))
      (node (ref "U2") (pin "30") (pinfunction "VSSM_30") (pintype "power_in"))
      (node (ref "U2") (pin "31") (pinfunction "VSSLSC_31") (pintype "power_in"))
      (node (ref "U2") (pin "32") (pinfunction "NC_32") (pintype "passive"))
      (node (ref "U2") (pin "33") (pinfunction "NC_33") (pintype "passive"))
      (node (ref "U2") (pin "34") (pinfunction "NC_34") (pintype "passive"))
      (node (ref "U2") (pin "35") (pinfunction "VSSLSC_35") (pintype "power_in"))
      (node (ref "U2") (pin "36") (pinfunction "NC_36") (pintype "passive"))
      (node (ref "U2") (pin "37") (pinfunction "VSSLCN_37") (pintype "power_in"))
      (node (ref "U2") (pin "41") (pinfunction "VSSM_41") (pintype "power_in"))
      (node (ref "U2") (pin "43") (pinfunction "NC_43") (pintype "passive"))
      (node (ref "U2") (pin "44") (pinfunction "NC_44") (pintype "passive"))
      (node (ref "U2") (pin "45") (pinfunction "NC_45") (pintype "passive"))
      (node (ref "U2") (pin "47") (pinfunction "NC_47") (pintype "passive"))
      (node (ref "U2") (pin "48") (pinfunction "VSSLSC_48") (pintype "power_in"))
      (node (ref "U2") (pin "68") (pinfunction "VSSM_68") (pintype "power_in"))
      (node (ref "U2") (pin "69") (pinfunction "NC_69") (pintype "passive"))
      (node (ref "U2") (pin "74") (pinfunction "NC_74") (pintype "passive"))
      (node (ref "U2") (pin "79") (pinfunction "VSSM_79") (pintype "power_in"))
      (node (ref "U2") (pin "80") (pinfunction "NC_80") (pintype "passive"))
      (node (ref "U2") (pin "81") (pinfunction "VSSLSC_81") (pintype "power_in"))
      (node (ref "U2") (pin "82") (pinfunction "VSSLIF_82") (pintype "power_in"))
      (node (ref "U2") (pin "83") (pinfunction "VSSLIF_83") (pintype "power_in"))
      (node (ref "U2") (pin "84") (pinfunction "VSSLSC_84") (pintype "power_in"))
      (node (ref "U2") (pin "85") (pinfunction "NC_85") (pintype "passive"))
      (node (ref "U2") (pin "87") (pinfunction "VSSLSC_87") (pintype "power_in"))
      (node (ref "U2") (pin "89") (pinfunction "VSSM_89") (pintype "power_in"))
      (node (ref "U2") (pin "9") (pinfunction "NC_9") (pintype "passive"))
      (node (ref "U2") (pin "90") (pinfunction "VSSM_90") (pintype "power_in"))
      (node (ref "U2") (pin "91") (pinfunction "NC_91") (pintype "passive"))
      (node (ref "U2") (pin "92") (pinfunction "VSSLIF_92") (pintype "power_in"))
      (node (ref "U2") (pin "93") (pinfunction "VSSLIF_93") (pintype "power_in"))
      (node (ref "U2") (pin "94") (pinfunction "VSSLIF_94") (pintype "power_in"))
      (node (ref "U2") (pin "95") (pinfunction "VSSLIF_95") (pintype "power_in"))
      (node (ref "U2") (pin "96") (pinfunction "VSSLIF_96") (pintype "power_in"))
      (node (ref "U2") (pin "97") (pinfunction "VSSLCN_97") (pintype "power_in"))
      (node (ref "U2") (pin "99") (pinfunction "VSSLSC_99") (pintype "power_in"))
      (node (ref "U3") (pin "2") (pinfunction "GND_2") (pintype "power_in"))
      (node (ref "U4") (pin "2") (pinfunction "GND_2") (pintype "power_in"))
      (node (ref "U4") (pin "4") (pinfunction "BYPASS_4") (pintype "bidirectional"))
      (node (ref "U5") (pin "1") (pinfunction "GND_1") (pintype "power_in"))
      (node (ref "U6") (pin "1") (pinfunction "1DIR_1") (pintype "input"))
      (node (ref "U6") (pin "10") (pinfunction "GND_10") (pintype "power_in"))
      (node (ref "U6") (pin "15") (pinfunction "GND_15") (pintype "power_in"))
      (node (ref "U6") (pin "21") (pinfunction "GND_21") (pintype "power_in"))
      (node (ref "U6") (pin "24") (pinfunction "2DIR_24") (pintype "input"))
      (node (ref "U6") (pin "28") (pinfunction "GND_28") (pintype "power_in"))
      (node (ref "U6") (pin "34") (pinfunction "GND_34") (pintype "power_in"))
      (node (ref "U6") (pin "39") (pinfunction "GND_39") (pintype "power_in"))
      (node (ref "U6") (pin "4") (pinfunction "GND_4") (pintype "power_in"))
      (node (ref "U6") (pin "45") (pinfunction "GND_45") (pintype "power_in"))
      (node (ref "U7") (pin "2") (pinfunction "GND_2") (pintype "power_in"))
      (node (ref "U7") (pin "4") (pinfunction "BYPASS_4") (pintype "bidirectional"))
      (node (ref "U8") (pin "2") (pinfunction "GND_2") (pintype "passive"))
      (node (ref "U9") (pin "7") (pinfunction "GND_7") (pintype "power_in"))
    )
    (net (code "46") (name "Net-(U2-DLOMC)") (class "Default")
      (node (ref "U2") (pin "39") (pinfunction "DLOMC_39") (pintype "output"))
      (node (ref "U6") (pin "6") (pinfunction "1B4_6") (pintype "bidirectional"))
    )
    (net (code "47") (name "Net-(U2-DLOMD)") (class "Default")
      (node (ref "U2") (pin "50") (pinfunction "DLOMD_50") (pintype "output"))
      (node (ref "U6") (pin "9") (pinfunction "1B6_9") (pintype "bidirectional"))
    )
    (net (code "48") (name "Net-(U2-DLOME)") (class "Default")
      (node (ref "U2") (pin "58") (pinfunction "DLOME_58") (pintype "output"))
      (node (ref "U6") (pin "12") (pinfunction "1B8_12") (pintype "bidirectional"))
    )
    (net (code "49") (name "Net-(U2-DLOMF)") (class "Default")
      (node (ref "U2") (pin "62") (pinfunction "DLOMF_62") (pintype "output"))
      (node (ref "U6") (pin "14") (pinfunction "2B2_14") (pintype "bidirectional"))
    )
    (net (code "50") (name "Net-(U2-DLOMG)") (class "Default")
      (node (ref "U2") (pin "66") (pinfunction "DLOMG_66") (pintype "output"))
      (node (ref "U6") (pin "17") (pinfunction "2B4_17") (pintype "bidirectional"))
    )
    (net (code "51") (name "Net-(U2-DLOPC)") (class "Default")
      (node (ref "U2") (pin "40") (pinfunction "DLOPC_40") (pintype "output"))
      (node (ref "U6") (pin "5") (pinfunction "1B3_5") (pintype "bidirectional"))
    )
    (net (code "52") (name "Net-(U2-DLOPD)") (class "Default")
      (node (ref "U2") (pin "51") (pinfunction "DLOPD_51") (pintype "output"))
      (node (ref "U6") (pin "8") (pinfunction "1B5_8") (pintype "bidirectional"))
    )
    (net (code "53") (name "Net-(U2-DLOPE)") (class "Default")
      (node (ref "U2") (pin "59") (pinfunction "DLOPE_59") (pintype "output"))
      (node (ref "U6") (pin "11") (pinfunction "1B7_11") (pintype "bidirectional"))
    )
    (net (code "54") (name "Net-(U2-DLOPF)") (class "Default")
      (node (ref "U2") (pin "63") (pinfunction "DLOPF_63") (pintype "output"))
      (node (ref "U6") (pin "13") (pinfunction "2B1_13") (pintype "bidirectional"))
    )
    (net (code "55") (name "Net-(U2-VBGR)") (class "Default")
      (node (ref "C40") (pin "1") (pinfunction "1_1") (pintype "passive"))
      (node (ref "U2") (pin "27") (pinfunction "VBGR_27") (pintype "output"))
    )
    (net (code "56") (name "Net-(U2-VLOADLM)") (class "Default")
      (node (ref "C37") (pin "1") (pinfunction "1_1") (pintype "passive"))
      (node (ref "U2") (pin "2") (pinfunction "VLOADLM_2") (pintype "output"))
    )
    (net (code "57") (name "Net-(U2-VRLFR)") (class "Default")
      (node (ref "C39") (pin "1") (pinfunction "1_1") (pintype "passive"))
      (node (ref "U2") (pin "4") (pinfunction "VRLFR_4") (pintype "output"))
    )
    (net (code "58") (name "Net-(U2-VRLST)") (class "Default")
      (node (ref "C38") (pin "1") (pinfunction "1_1") (pintype "passive"))
      (node (ref "U2") (pin "12") (pinfunction "VRLST_12") (pintype "output"))
    )
    (net (code "59") (name "Net-(U3-BYPASS)") (class "Default")
      (node (ref "C1") (pin "1") (pinfunction "1_1") (pintype "passive"))
      (node (ref "U3") (pin "4") (pinfunction "BYPASS_4") (pintype "bidirectional"))
    )
    (net (code "60") (name "Net-(U3-OUT)") (class "Default")
      (node (ref "C3") (pin "2") (pinfunction "2_2") (pintype "passive"))
      (node (ref "R30") (pin "1") (pinfunction "1_1") (pintype "passive"))
      (node (ref "U3") (pin "5") (pinfunction "OUT_5") (pintype "output"))
    )
    (net (code "61") (name "Net-(U4-OUT)") (class "Default")
      (node (ref "C5") (pin "2") (pinfunction "2_2") (pintype "passive"))
      (node (ref "R28") (pin "1") (pinfunction "1_1") (pintype "passive"))
      (node (ref "U4") (pin "5") (pinfunction "OUT_5") (pintype "output"))
    )
    (net (code "62") (name "Net-(U6-1A3)") (class "Default")
      (node (ref "R9") (pin "1") (pinfunction "1_1") (pintype "passive"))
      (node (ref "U6") (pin "44") (pinfunction "1A3_44") (pintype "bidirectional"))
    )
    (net (code "63") (name "Net-(U6-1A4)") (class "Default")
      (node (ref "R10") (pin "1") (pinfunction "1_1") (pintype "passive"))
      (node (ref "U6") (pin "43") (pinfunction "1A4_43") (pintype "bidirectional"))
    )
    (net (code "64") (name "Net-(U6-1A5)") (class "Default")
      (node (ref "R16") (pin "1") (pinfunction "1_1") (pintype "passive"))
      (node (ref "U6") (pin "41") (pinfunction "1A5_41") (pintype "bidirectional"))
    )
    (net (code "65") (name "Net-(U6-1A6)") (class "Default")
      (node (ref "R17") (pin "1") (pinfunction "1_1") (pintype "passive"))
      (node (ref "U6") (pin "40") (pinfunction "1A6_40") (pintype "bidirectional"))
    )
    (net (code "66") (name "Net-(U6-1A7)") (class "Default")
      (node (ref "R18") (pin "1") (pinfunction "1_1") (pintype "passive"))
      (node (ref "U6") (pin "38") (pinfunction "1A7_38") (pintype "bidirectional"))
    )
    (net (code "67") (name "Net-(U6-1A8)") (class "Default")
      (node (ref "R19") (pin "1") (pinfunction "1_1") (pintype "passive"))
      (node (ref "U6") (pin "37") (pinfunction "1A8_37") (pintype "bidirectional"))
    )
    (net (code "68") (name "Net-(U6-2A1)") (class "Default")
      (node (ref "R20") (pin "1") (pinfunction "1_1") (pintype "passive"))
      (node (ref "U6") (pin "36") (pinfunction "2A1_36") (pintype "bidirectional"))
    )
    (net (code "69") (name "Net-(U6-2A2)") (class "Default")
      (node (ref "R21") (pin "1") (pinfunction "1_1") (pintype "passive"))
      (node (ref "U6") (pin "35") (pinfunction "2A2_35") (pintype "bidirectional"))
    )
    (net (code "70") (name "Net-(U6-2A3)") (class "Default")
      (node (ref "R22") (pin "1") (pinfunction "1_1") (pintype "passive"))
      (node (ref "U6") (pin "33") (pinfunction "2A3_33") (pintype "bidirectional"))
    )
    (net (code "71") (name "Net-(U6-2A4)") (class "Default")
      (node (ref "R23") (pin "1") (pinfunction "1_1") (pintype "passive"))
      (node (ref "U6") (pin "32") (pinfunction "2A4_32") (pintype "bidirectional"))
    )
    (net (code "72") (name "Net-(U6-2A5)") (class "Default")
      (node (ref "R24") (pin "1") (pinfunction "1_1") (pintype "passive"))
      (node (ref "U6") (pin "30") (pinfunction "2A5_30") (pintype "bidirectional"))
    )
    (net (code "73") (name "Net-(U6-2A6)") (class "Default")
      (node (ref "R25") (pin "1") (pinfunction "1_1") (pintype "passive"))
      (node (ref "U6") (pin "29") (pinfunction "2A6_29") (pintype "bidirectional"))
    )
    (net (code "74") (name "Net-(U6-2A7)") (class "Default")
      (node (ref "R26") (pin "1") (pinfunction "1_1") (pintype "passive"))
      (node (ref "U6") (pin "27") (pinfunction "2A7_27") (pintype "bidirectional"))
    )
    (net (code "75") (name "Net-(U6-2A8)") (class "Default")
      (node (ref "R27") (pin "1") (pinfunction "1_1") (pintype "passive"))
      (node (ref "U6") (pin "26") (pinfunction "2A8_26") (pintype "bidirectional"))
    )
    (net (code "76") (name "Net-(U7-OUT)") (class "Default")
      (node (ref "C6") (pin "2") (pinfunction "2_2") (pintype "passive"))
      (node (ref "R29") (pin "1") (pinfunction "1_1") (pintype "passive"))
      (node (ref "U7") (pin "5") (pinfunction "OUT_5") (pintype "output"))
    )
    (net (code "77") (name "Net-(U10-Y)") (class "Default")
      (node (ref "R12") (pin "1") (pinfunction "1_1") (pintype "passive"))
      (node (ref "U10") (pin "4") (pinfunction "Y_4") (pintype "output"))
      (node (ref "U6") (pin "25") (pinfunction "2~{OE}_25") (pintype "input"))
      (node (ref "U6") (pin "48") (pinfunction "1~{OE}_48") (pintype "input"))
    )
    (net (code "78") (name "unconnected-(P2-Pad5)") (class "Default")
      (node (ref "P2") (pin "5") (pinfunction "5_5") (pintype "passive"))
    )
    (net (code "79") (name "unconnected-(P2-Pad6)") (class "Default")
      (node (ref "P2") (pin "6") (pinfunction "6_6") (pintype "passive"))
    )
    (net (code "80") (name "unconnected-(P2-Pad7)") (class "Default")
      (node (ref "P2") (pin "7") (pinfunction "7_7") (pintype "passive"))
    )
    (net (code "81") (name "unconnected-(P2-Pad8)") (class "Default")
      (node (ref "P2") (pin "8") (pinfunction "8_8") (pintype "passive"))
    )
    (net (code "82") (name "unconnected-(P2-Pad9)") (class "Default")
      (node (ref "P2") (pin "9") (pinfunction "9_9") (pintype "passive"))
    )
    (net (code "83") (name "unconnected-(P2-Pad10)") (class "Default")
      (node (ref "P2") (pin "10") (pinfunction "10_10") (pintype "passive"))
    )
    (net (code "84") (name "unconnected-(P2-Pad11)") (class "Default")
      (node (ref "P2") (pin "11") (pinfunction "11_11") (pintype "passive"))
    )
    (net (code "85") (name "unconnected-(P2-Pad12)") (class "Default")
      (node (ref "P2") (pin "12") (pinfunction "12_12") (pintype "passive"))
    )
    (net (code "86") (name "unconnected-(P2-Pad13)") (class "Default")
      (node (ref "P2") (pin "13") (pinfunction "13_13") (pintype "passive"))
    )
    (net (code "87") (name "unconnected-(P2-Pad14)") (class "Default")
      (node (ref "P2") (pin "14") (pinfunction "14_14") (pintype "passive"))
    )
    (net (code "88") (name "unconnected-(P2-Pad15)") (class "Default")
      (node (ref "P2") (pin "15") (pinfunction "15_15") (pintype "passive"))
    )
    (net (code "89") (name "unconnected-(P2-Pad16)") (class "Default")
      (node (ref "P2") (pin "16") (pinfunction "16_16") (pintype "passive"))
    )
    (net (code "90") (name "unconnected-(P2-Pad17)") (class "Default")
      (node (ref "P2") (pin "17") (pinfunction "17_17") (pintype "passive"))
    )
    (net (code "91") (name "unconnected-(P2-Pad18)") (class "Default")
      (node (ref "P2") (pin "18") (pinfunction "18_18") (pintype "passive"))
    )
    (net (code "92") (name "unconnected-(P2-Pad21)") (class "Default")
      (node (ref "P2") (pin "21") (pinfunction "21_21") (pintype "passive"))
    )
    (net (code "93") (name "unconnected-(P2-Pad22)") (class "Default")
      (node (ref "P2") (pin "22") (pinfunction "22_22") (pintype "passive"))
    )
    (net (code "94") (name "unconnected-(P2-Pad24)") (class "Default")
      (node (ref "P2") (pin "24") (pinfunction "24_24") (pintype "passive"))
    )
    (net (code "95") (name "unconnected-(P2-Pad30)") (class "Default")
      (node (ref "P2") (pin "30") (pinfunction "30_30") (pintype "passive"))
    )
    (net (code "96") (name "unconnected-(P2-Pad31)") (class "Default")
      (node (ref "P2") (pin "31") (pinfunction "31_31") (pintype "passive"))
    )
    (net (code "97") (name "unconnected-(P2-Pad32)") (class "Default")
      (node (ref "P2") (pin "32") (pinfunction "32_32") (pintype "passive"))
    )
    (net (code "98") (name "unconnected-(P8-2-Pad3)") (class "Default")
      (node (ref "P8") (pin "3") (pinfunction "2_3") (pintype "passive"))
    )
    (net (code "99") (name "unconnected-(P8-3-Pad5)") (class "Default")
      (node (ref "P8") (pin "5") (pinfunction "3_5") (pintype "passive"))
    )
    (net (code "100") (name "unconnected-(P8-4-Pad7)") (class "Default")
      (node (ref "P8") (pin "7") (pinfunction "4_7") (pintype "passive"))
    )
    (net (code "101") (name "unconnected-(P8-5-Pad9)") (class "Default")
      (node (ref "P8") (pin "9") (pinfunction "5_9") (pintype "passive"))
    )
    (net (code "102") (name "unconnected-(P8-7-Pad13)") (class "Default")
      (node (ref "P8") (pin "13") (pinfunction "7_13") (pintype "passive"))
    )
    (net (code "103") (name "unconnected-(P8-8-Pad15)") (class "Default")
      (node (ref "P8") (pin "15") (pinfunction "8_15") (pintype "passive"))
    )
    (net (code "104") (name "unconnected-(P8-9-Pad17)") (class "Default")
      (node (ref "P8") (pin "17") (pinfunction "9_17") (pintype "passive"))
    )
    (net (code "105") (name "unconnected-(P8-10-Pad19)") (class "Default")
      (node (ref "P8") (pin "19") (pinfunction "10_19") (pintype "passive"))
    )
    (net (code "106") (name "unconnected-(P8-12-Pad23)") (class "Default")
      (node (ref "P8") (pin "23") (pinfunction "12_23") (pintype "passive"))
    )
    (net (code "107") (name "unconnected-(P8-13-Pad25)") (class "Default")
      (node (ref "P8") (pin "25") (pinfunction "13_25") (pintype "passive"))
    )
    (net (code "108") (name "unconnected-(P8-16-Pad31)") (class "Default")
      (node (ref "P8") (pin "31") (pinfunction "16_31") (pintype "passive"))
    )
    (net (code "109") (name "unconnected-(P8-17-Pad33)") (class "Default")
      (node (ref "P8") (pin "33") (pinfunction "17_33") (pintype "passive"))
    )
    (net (code "110") (name "unconnected-(P8-18-Pad35)") (class "Default")
      (node (ref "P8") (pin "35") (pinfunction "18_35") (pintype "passive"))
    )
    (net (code "111") (name "unconnected-(P8-19-Pad37)") (class "Default")
      (node (ref "P8") (pin "37") (pinfunction "19_37") (pintype "passive"))
    )
    (net (code "112") (name "unconnected-(P8-27-Pad4)") (class "Default")
      (node (ref "P8") (pin "4") (pinfunction "27_4") (pintype "passive"))
    )
    (net (code "113") (name "unconnected-(P8-28-Pad6)") (class "Default")
      (node (ref "P8") (pin "6") (pinfunction "28_6") (pintype "passive"))
    )
    (net (code "114") (name "unconnected-(P8-29-Pad8)") (class "Default")
      (node (ref "P8") (pin "8") (pinfunction "29_8") (pintype "passive"))
    )
    (net (code "115") (name "unconnected-(P8-30-Pad10)") (class "Default")
      (node (ref "P8") (pin "10") (pinfunction "30_10") (pintype "passive"))
    )
    (net (code "116") (name "unconnected-(P8-32-Pad14)") (class "Default")
      (node (ref "P8") (pin "14") (pinfunction "32_14") (pintype "passive"))
    )
    (net (code "117") (name "unconnected-(P8-33-Pad16)") (class "Default")
      (node (ref "P8") (pin "16") (pinfunction "33_16") (pintype "passive"))
    )
    (net (code "118") (name "unconnected-(P8-34-Pad18)") (class "Default")
      (node (ref "P8") (pin "18") (pinfunction "34_18") (pintype "passive"))
    )
    (net (code "119") (name "unconnected-(P8-36-Pad22)") (class "Default")
      (node (ref "P8") (pin "22") (pinfunction "36_22") (pintype "passive"))
    )
    (net (code "120") (name "unconnected-(P8-37-Pad24)") (class "Default")
      (node (ref "P8") (pin "24") (pinfunction "37_24") (pintype "passive"))
    )
    (net (code "121") (name "unconnected-(P8-38-Pad26)") (class "Default")
      (node (ref "P8") (pin "26") (pinfunction "38_26") (pintype "passive"))
    )
    (net (code "122") (name "unconnected-(P8-41-Pad32)") (class "Default")
      (node (ref "P8") (pin "32") (pinfunction "41_32") (pintype "passive"))
    )
    (net (code "123") (name "unconnected-(P8-42-Pad34)") (class "Default")
      (node (ref "P8") (pin "34") (pinfunction "42_34") (pintype "passive"))
    )
    (net (code "124") (name "unconnected-(P8-43-Pad36)") (class "Default")
      (node (ref "P8") (pin "36") (pinfunction "43_36") (pintype "passive"))
    )
    (net (code "125") (name "unconnected-(P8-44-Pad38)") (class "Default")
      (node (ref "P8") (pin "38") (pinfunction "44_38") (pintype "passive"))
    )
    (net (code "126") (name "unconnected-(TP1-0-Pad1)") (class "Default")
      (node (ref "TP1") (pin "1") (pinfunction "0_1") (pintype "passive"))
    )
    (net (code "127") (name "unconnected-(TP2-0-Pad1)") (class "Default")
      (node (ref "TP2") (pin "1") (pinfunction "0_1") (pintype "passive"))
    )
    (net (code "128") (name "unconnected-(TP3-0-Pad1)") (class "Default")
      (node (ref "TP3") (pin "1") (pinfunction "0_1") (pintype "passive"))
    )
    (net (code "129") (name "unconnected-(TP4-0-Pad1)") (class "Default")
      (node (ref "TP4") (pin "1") (pinfunction "0_1") (pintype "passive"))
    )
    (net (code "130") (name "unconnected-(U2-DLCKM-Pad54)") (class "Default")
      (node (ref "U2") (pin "54") (pinfunction "DLCKM_54") (pintype "output"))
    )
    (net (code "131") (name "unconnected-(U2-DLOMA-Pad17)") (class "Default")
      (node (ref "U2") (pin "17") (pinfunction "DLOMA_17") (pintype "output"))
    )
    (net (code "132") (name "unconnected-(U2-DLOMH-Pad77)") (class "Default")
      (node (ref "U2") (pin "77") (pinfunction "DLOMH_77") (pintype "output"))
    )
    (net (code "133") (name "unconnected-(U2-DLOPA-Pad18)") (class "Default")
      (node (ref "U2") (pin "18") (pinfunction "DLOPA_18") (pintype "output"))
    )
    (net (code "134") (name "unconnected-(U2-DLOPH-Pad78)") (class "Default")
      (node (ref "U2") (pin "78") (pinfunction "DLOPH_78") (pintype "output"))
    )
    (net (code "135") (name "unconnected-(U2-DMCKN-Pad111)") (class "Default")
      (node (ref "U2") (pin "111") (pinfunction "DMCKN_111") (pintype "output"))
    )
    (net (code "136") (name "unconnected-(U2-DMCKP-Pad103)") (class "Default")
      (node (ref "U2") (pin "103") (pinfunction "DMCKP_103") (pintype "output"))
    )
    (net (code "137") (name "unconnected-(U2-DMO1N-Pad110)") (class "Default")
      (node (ref "U2") (pin "110") (pinfunction "DMO1N_110") (pintype "output"))
    )
    (net (code "138") (name "unconnected-(U2-DMO1P-Pad102)") (class "Default")
      (node (ref "U2") (pin "102") (pinfunction "DMO1P_102") (pintype "output"))
    )
    (net (code "139") (name "unconnected-(U2-DMO2N-Pad112)") (class "Default")
      (node (ref "U2") (pin "112") (pinfunction "DMO2N_112") (pintype "output"))
    )
    (net (code "140") (name "unconnected-(U2-DMO2P-Pad104)") (class "Default")
      (node (ref "U2") (pin "104") (pinfunction "DMO2P_104") (pintype "output"))
    )
    (net (code "141") (name "unconnected-(U2-DMO3N-Pad109)") (class "Default")
      (node (ref "U2") (pin "109") (pinfunction "DMO3N_109") (pintype "output"))
    )
    (net (code "142") (name "unconnected-(U2-DMO3P-Pad101)") (class "Default")
      (node (ref "U2") (pin "101") (pinfunction "DMO3P_101") (pintype "output"))
    )
    (net (code "143") (name "unconnected-(U2-DMO4N-Pad113)") (class "Default")
      (node (ref "U2") (pin "113") (pinfunction "DMO4N_113") (pintype "output"))
    )
    (net (code "144") (name "unconnected-(U2-DMO4P-Pad105)") (class "Default")
      (node (ref "U2") (pin "105") (pinfunction "DMO4P_105") (pintype "output"))
    )
    (net (code "145") (name "unconnected-(U2-SDO-Pad52)") (class "Default")
      (node (ref "U2") (pin "52") (pinfunction "SDO_52") (pintype "output"))
    )
    (net (code "146") (name "unconnected-(U2-TAMON-Pad26)") (class "Default")
      (node (ref "U2") (pin "26") (pinfunction "TAMON_26") (pintype "output"))
    )
    (net (code "147") (name "unconnected-(U2-TENABLE-Pad49)") (class "Default")
      (node (ref "U2") (pin "49") (pinfunction "TENABLE_49") (pintype "input+no_connect"))
    )
    (net (code "148") (name "unconnected-(U2-TOUT-Pad65)") (class "Default")
      (node (ref "U2") (pin "65") (pinfunction "TOUT_65") (pintype "output"))
    )
    (net (code "149") (name "unconnected-(U2-XTRIG-Pad76)") (class "Default")
      (node (ref "U2") (pin "76") (pinfunction "XTRIG_76") (pintype "input+no_connect"))
    )
    (net (code "150") (name "unconnected-(U6-1A1-Pad47)") (class "Default")
      (node (ref "U6") (pin "47") (pinfunction "1A1_47") (pintype "bidirectional"))
    )
    (net (code "151") (name "unconnected-(U6-1A2-Pad46)") (class "Default")
      (node (ref "U6") (pin "46") (pinfunction "1A2_46") (pintype "bidirectional"))
    )
    (net (code "152") (name "unconnected-(U6-1B1-Pad2)") (class "Default")
      (node (ref "U6") (pin "2") (pinfunction "1B1_2") (pintype "bidirectional"))
    )
    (net (code "153") (name "unconnected-(U6-1B2-Pad3)") (class "Default")
      (node (ref "U6") (pin "3") (pinfunction "1B2_3") (pintype "bidirectional"))
    )
    (net (code "154") (name "unconnected-(U9-NC-Pad6)") (class "Default")
      (node (ref "U9") (pin "6") (pinfunction "NC_6") (pintype "passive"))
    )
    (net (code "155") (name "unconnected-(U9-NC-Pad9)") (class "Default")
      (node (ref "U9") (pin "9") (pinfunction "NC_9") (pintype "passive"))
    )
  )
)
